# IRtestCircuit.net
KiCad netlist of a schematic drawn in EAGLE
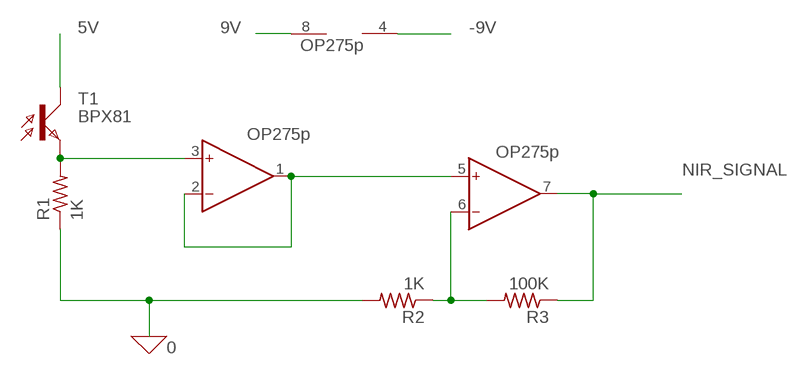
[diagram p0: schematic, sheet 1]

(export (version "E")
  (design (tool "Eeschema 10.0.6"))
  (components
    (comp (ref "IC1")
      (value "OP275p")
      (footprint "eagle-import:DIL08")
      (fields (field (name "MF") "ALTERA CORPORATION") (field (name "MPN") "AD746JNZ"))
      (libsource (lib "eagle-import") (part "AD746N"))
    )
    (comp (ref "R1")
      (value "1K")
      (footprint "eagle-import:0207_10")
      (libsource (lib "eagle-import") (part "R-US_0207/10"))
    )
    (comp (ref "R2")
      (value "1K")
      (footprint "eagle-import:0207_10")
      (libsource (lib "eagle-import") (part "R-US_0207/10"))
    )
    (comp (ref "R3")
      (value "100K")
      (footprint "eagle-import:0207_10")
      (libsource (lib "eagle-import") (part "R-US_0207/10"))
    )
    (comp (ref "T1")
      (value "BPX81")
      (footprint "eagle-import:BPX81")
      (libsource (lib "eagle-import") (part "BPX81"))
    )
  )
  (nets
    (net (code "1") (name "/-9V") (class "Default")
      (node (ref "IC1") (pin "4") (pinfunction "V-_4") (pintype "power_in"))
    )
    (net (code "2") (name "/5V") (class "Default")
      (node (ref "T1") (pin "C") (pinfunction "C_C") (pintype "passive"))
    )
    (net (code "3") (name "/9V") (class "Default")
      (node (ref "IC1") (pin "8") (pinfunction "V+_8") (pintype "power_in"))
    )
    (net (code "4") (name "/NIR_SIGNAL") (class "Default")
      (node (ref "IC1") (pin "7") (pinfunction "OUT_7") (pintype "output"))
      (node (ref "R3") (pin "1") (pinfunction "1_1") (pintype "passive"))
    )
    (net (code "5") (name "GND") (class "Default")
      (node (ref "R1") (pin "1") (pinfunction "1_1") (pintype "passive"))
      (node (ref "R2") (pin "2") (pinfunction "2_2") (pintype "passive"))
    )
    (net (code "6") (name "Net-(IC1A-IN+)") (class "Default")
      (node (ref "IC1") (pin "3") (pinfunction "IN+_3") (pintype "input"))
      (node (ref "R1") (pin "2") (pinfunction "2_2") (pintype "passive"))
      (node (ref "T1") (pin "E") (pinfunction "E_E") (pintype "passive"))
    )
    (net (code "7") (name "Net-(IC1A-IN-)") (class "Default")
      (node (ref "IC1") (pin "1") (pinfunction "OUT_1") (pintype "output"))
      (node (ref "IC1") (pin "2") (pinfunction "IN-_2") (pintype "input"))
      (node (ref "IC1") (pin "5") (pinfunction "IN+_5") (pintype "input"))
    )
    (net (code "8") (name "Net-(IC1B-IN-)") (class "Default")
      (node (ref "IC1") (pin "6") (pinfunction "IN-_6") (pintype "input"))
      (node (ref "R2") (pin "1") (pinfunction "1_1") (pintype "passive"))
      (node (ref "R3") (pin "2") (pinfunction "2_2") (pintype "passive"))
    )
  )
)
